# arduino_shield.net
KiCad netlist of a schematic drawn in EAGLE
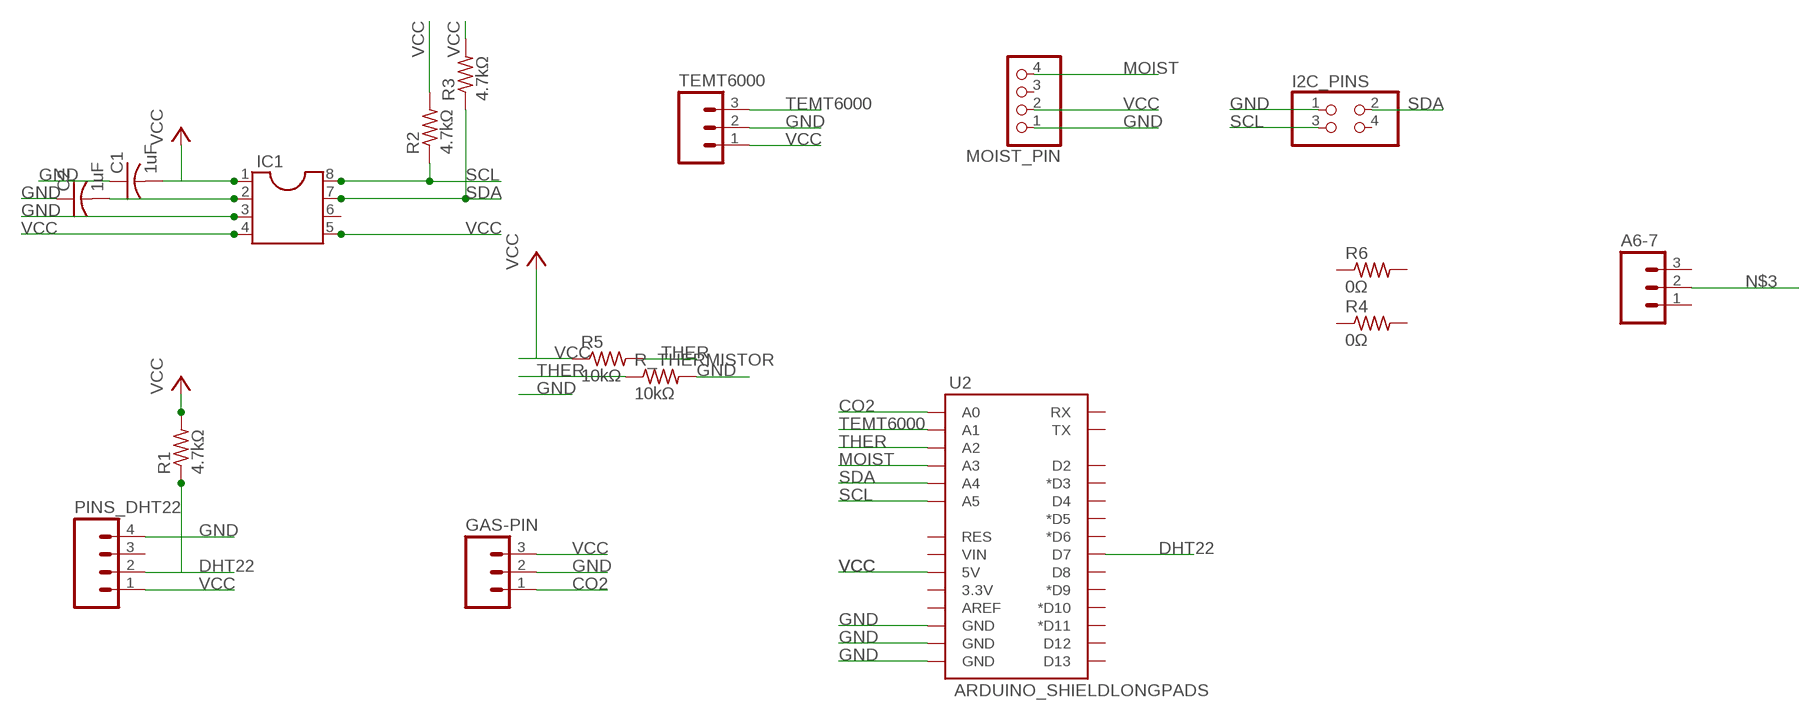
[diagram p0: schematic, sheet 1]

(export (version "E")
  (design (tool "Eeschema 10.0.6"))
  (components
    (comp (ref "A6-7")
      (value "M03LOCK_LONGPADS")
      (footprint "eagle-import:1X03_LOCK_LONGPADS")
      (libsource (lib "eagle-import") (part "M03LOCK_LONGPADS"))
    )
    (comp (ref "C1")
      (value "1uF")
      (footprint "eagle-import:C1206")
      (libsource (lib "eagle-import") (part "C-USC1206"))
    )
    (comp (ref "C2")
      (value "1uF")
      (footprint "eagle-import:C1206")
      (libsource (lib "eagle-import") (part "C-USC1206"))
    )
    (comp (ref "GAS-PIN")
      (value "M03LOCK_LONGPADS")
      (footprint "eagle-import:1X03_LOCK_LONGPADS")
      (libsource (lib "eagle-import") (part "M03LOCK_LONGPADS"))
    )
    (comp (ref "I2C_PINS")
      (value "PINHD-2X2")
      (footprint "eagle-import:2X02")
      (libsource (lib "eagle-import") (part "PINHD-2X2"))
    )
    (comp (ref "IC1")
      (value "DIL8S")
      (footprint "eagle-import:SOCKET-08")
      (libsource (lib "eagle-import") (part "DIL8S"))
    )
    (comp (ref "MOIST_PIN")
      (value "PINHD-1X4M")
      (footprint "eagle-import:1X04M")
      (libsource (lib "eagle-import") (part "PINHD-1X4M"))
    )
    (comp (ref "PINS_DHT22")
      (value "M04LOCK_LONGPADS")
      (footprint "eagle-import:1X04_LOCK_LONGPADS")
      (libsource (lib "eagle-import") (part "M04LOCK_LONGPADS"))
    )
    (comp (ref "R1")
      (value "4.7kΩ")
      (footprint "eagle-import:M1206")
      (libsource (lib "eagle-import") (part "R-US_M1206"))
    )
    (comp (ref "R2")
      (value "4.7kΩ")
      (footprint "eagle-import:M1206")
      (libsource (lib "eagle-import") (part "R-US_M1206"))
    )
    (comp (ref "R3")
      (value "4.7kΩ")
      (footprint "eagle-import:M1206")
      (libsource (lib "eagle-import") (part "R-US_M1206"))
    )
    (comp (ref "R4")
      (value "0Ω")
      (footprint "eagle-import:M1206")
      (libsource (lib "eagle-import") (part "R-US_M1206"))
    )
    (comp (ref "R5")
      (value "10kΩ")
      (footprint "eagle-import:M1206")
      (libsource (lib "eagle-import") (part "R-US_M1206"))
    )
    (comp (ref "R6")
      (value "0Ω")
      (footprint "eagle-import:M1206")
      (libsource (lib "eagle-import") (part "R-US_M1206"))
    )
    (comp (ref "R_THERMISTOR")
      (value "10kΩ")
      (footprint "eagle-import:M1206")
      (libsource (lib "eagle-import") (part "R-US_M1206"))
    )
    (comp (ref "TEMT6000")
      (value "M03LOCK_LONGPADS")
      (footprint "eagle-import:1X03_LOCK_LONGPADS")
      (libsource (lib "eagle-import") (part "M03LOCK_LONGPADS"))
    )
    (comp (ref "U2")
      (value "ARDUINO_SHIELDLONGPADS")
      (footprint "eagle-import:DUEMILANOVE_SHIELD_LONGPADS")
      (libsource (lib "eagle-import") (part "ARDUINO_SHIELDLONGPADS"))
    )
  )
  (nets
    (net (code "1") (name "/CO2") (class "Default")
      (node (ref "GAS-PIN") (pin "1") (pinfunction "1_1") (pintype "passive"))
      (node (ref "U2") (pin "A0") (pinfunction "A0_A0") (pintype "bidirectional"))
    )
    (net (code "2") (name "/DHT22") (class "Default")
      (node (ref "PINS_DHT22") (pin "2") (pinfunction "2_2") (pintype "passive"))
      (node (ref "R1") (pin "1") (pinfunction "1_1") (pintype "passive"))
      (node (ref "U2") (pin "D7") (pinfunction "D7_D7") (pintype "bidirectional"))
    )
    (net (code "3") (name "/GND") (class "Default")
      (node (ref "C1") (pin "1") (pinfunction "1_1") (pintype "passive"))
      (node (ref "C2") (pin "1") (pinfunction "1_1") (pintype "passive"))
      (node (ref "GAS-PIN") (pin "2") (pinfunction "2_2") (pintype "passive"))
      (node (ref "I2C_PINS") (pin "1") (pinfunction "1_1") (pintype "passive"))
      (node (ref "IC1") (pin "3") (pinfunction "3_3") (pintype "passive"))
      (node (ref "MOIST_PIN") (pin "1") (pinfunction "1_1") (pintype "passive"))
      (node (ref "PINS_DHT22") (pin "4") (pinfunction "4_4") (pintype "passive"))
      (node (ref "R_THERMISTOR") (pin "2") (pinfunction "2_2") (pintype "passive"))
      (node (ref "TEMT6000") (pin "2") (pinfunction "2_2") (pintype "passive"))
      (node (ref "U2") (pin "GND@0") (pinfunction "GND_GND@0") (pintype "bidirectional"))
      (node (ref "U2") (pin "GND@1") (pinfunction "GND_GND@1") (pintype "bidirectional"))
      (node (ref "U2") (pin "GND@2") (pinfunction "GND_GND@2") (pintype "bidirectional"))
    )
    (net (code "4") (name "/MOIST") (class "Default")
      (node (ref "MOIST_PIN") (pin "4") (pinfunction "4_4") (pintype "passive"))
      (node (ref "U2") (pin "A3") (pinfunction "A3_A3") (pintype "bidirectional"))
    )
    (net (code "5") (name "/N$3") (class "Default")
      (node (ref "A6-7") (pin "2") (pinfunction "2_2") (pintype "passive"))
    )
    (net (code "6") (name "/SCL") (class "Default")
      (node (ref "I2C_PINS") (pin "3") (pinfunction "3_3") (pintype "passive"))
      (node (ref "IC1") (pin "8") (pinfunction "8_8") (pintype "passive"))
      (node (ref "R2") (pin "1") (pinfunction "1_1") (pintype "passive"))
      (node (ref "U2") (pin "A5") (pinfunction "A5_A5") (pintype "bidirectional"))
    )
    (net (code "7") (name "/SDA") (class "Default")
      (node (ref "I2C_PINS") (pin "2") (pinfunction "2_2") (pintype "passive"))
      (node (ref "IC1") (pin "7") (pinfunction "7_7") (pintype "passive"))
      (node (ref "R3") (pin "1") (pinfunction "1_1") (pintype "passive"))
      (node (ref "U2") (pin "A4") (pinfunction "A4_A4") (pintype "bidirectional"))
    )
    (net (code "8") (name "/TEMT6000") (class "Default")
      (node (ref "TEMT6000") (pin "3") (pinfunction "3_3") (pintype "passive"))
      (node (ref "U2") (pin "A1") (pinfunction "A1_A1") (pintype "bidirectional"))
    )
    (net (code "9") (name "/THER") (class "Default")
      (node (ref "R5") (pin "2") (pinfunction "2_2") (pintype "passive"))
      (node (ref "R_THERMISTOR") (pin "1") (pinfunction "1_1") (pintype "passive"))
      (node (ref "U2") (pin "A2") (pinfunction "A2_A2") (pintype "bidirectional"))
    )
    (net (code "10") (name "Net-(C2-Pad2)") (class "Default")
      (node (ref "C2") (pin "2") (pinfunction "2_2") (pintype "passive"))
      (node (ref "IC1") (pin "2") (pinfunction "2_2") (pintype "passive"))
    )
    (net (code "11") (name "VCC") (class "Default")
      (node (ref "C1") (pin "2") (pinfunction "2_2") (pintype "passive"))
      (node (ref "GAS-PIN") (pin "3") (pinfunction "3_3") (pintype "passive"))
      (node (ref "IC1") (pin "1") (pinfunction "1_1") (pintype "passive"))
      (node (ref "IC1") (pin "4") (pinfunction "4_4") (pintype "passive"))
      (node (ref "IC1") (pin "5") (pinfunction "5_5") (pintype "passive"))
      (node (ref "MOIST_PIN") (pin "2") (pinfunction "2_2") (pintype "passive"))
      (node (ref "PINS_DHT22") (pin "1") (pinfunction "1_1") (pintype "passive"))
      (node (ref "R1") (pin "2") (pinfunction "2_2") (pintype "passive"))
      (node (ref "R2") (pin "2") (pinfunction "2_2") (pintype "passive"))
      (node (ref "R3") (pin "2") (pinfunction "2_2") (pintype "passive"))
      (node (ref "R5") (pin "1") (pinfunction "1_1") (pintype "passive"))
      (node (ref "TEMT6000") (pin "1") (pinfunction "1_1") (pintype "passive"))
      (node (ref "U2") (pin "5V") (pinfunction "5V_5V") (pintype "bidirectional"))
    )
    (net (code "12") (name "unconnected-(A6-7-Pad1)") (class "Default")
      (node (ref "A6-7") (pin "1") (pinfunction "1_1") (pintype "passive"))
    )
    (net (code "13") (name "unconnected-(A6-7-Pad3)") (class "Default")
      (node (ref "A6-7") (pin "3") (pinfunction "3_3") (pintype "passive"))
    )
    (net (code "14") (name "unconnected-(I2C_PINS-Pad4)") (class "Default")
      (node (ref "I2C_PINS") (pin "4") (pinfunction "4_4") (pintype "passive"))
    )
    (net (code "15") (name "unconnected-(IC1-Pad6)") (class "Default")
      (node (ref "IC1") (pin "6") (pinfunction "6_6") (pintype "passive"))
    )
    (net (code "16") (name "unconnected-(MOIST_PIN-Pad3)") (class "Default")
      (node (ref "MOIST_PIN") (pin "3") (pinfunction "3_3") (pintype "passive"))
    )
    (net (code "17") (name "unconnected-(PINS_DHT22-Pad3)") (class "Default")
      (node (ref "PINS_DHT22") (pin "3") (pinfunction "3_3") (pintype "passive"))
    )
    (net (code "18") (name "unconnected-(R4-Pad1)") (class "Default")
      (node (ref "R4") (pin "1") (pinfunction "1_1") (pintype "passive"))
    )
    (net (code "19") (name "unconnected-(R4-Pad2)") (class "Default")
      (node (ref "R4") (pin "2") (pinfunction "2_2") (pintype "passive"))
    )
    (net (code "20") (name "unconnected-(R6-Pad1)") (class "Default")
      (node (ref "R6") (pin "1") (pinfunction "1_1") (pintype "passive"))
    )
    (net (code "21") (name "unconnected-(R6-Pad2)") (class "Default")
      (node (ref "R6") (pin "2") (pinfunction "2_2") (pintype "passive"))
    )
    (net (code "22") (name "unconnected-(U2-*D3-PadD3)") (class "Default")
      (node (ref "U2") (pin "D3") (pinfunction "*D3_D3") (pintype "bidirectional"))
    )
    (net (code "23") (name "unconnected-(U2-*D5-PadD5)") (class "Default")
      (node (ref "U2") (pin "D5") (pinfunction "*D5_D5") (pintype "bidirectional"))
    )
    (net (code "24") (name "unconnected-(U2-*D6-PadD6)") (class "Default")
      (node (ref "U2") (pin "D6") (pinfunction "*D6_D6") (pintype "bidirectional"))
    )
    (net (code "25") (name "unconnected-(U2-*D9-PadD9)") (class "Default")
      (node (ref "U2") (pin "D9") (pinfunction "*D9_D9") (pintype "bidirectional"))
    )
    (net (code "26") (name "unconnected-(U2-*D10-PadD10)") (class "Default")
      (node (ref "U2") (pin "D10") (pinfunction "*D10_D10") (pintype "bidirectional"))
    )
    (net (code "27") (name "unconnected-(U2-*D11-PadD11)") (class "Default")
      (node (ref "U2") (pin "D11") (pinfunction "*D11_D11") (pintype "bidirectional"))
    )
    (net (code "28") (name "unconnected-(U2-Pad3.3V)") (class "Default")
      (node (ref "U2") (pin "3.3V") (pinfunction "3.3V_3.3V") (pintype "bidirectional"))
    )
    (net (code "29") (name "unconnected-(U2-PadAREF)") (class "Default")
      (node (ref "U2") (pin "AREF") (pinfunction "AREF_AREF") (pintype "bidirectional"))
    )
    (net (code "30") (name "unconnected-(U2-PadD2)") (class "Default")
      (node (ref "U2") (pin "D2") (pinfunction "D2_D2") (pintype "bidirectional"))
    )
    (net (code "31") (name "unconnected-(U2-PadD4)") (class "Default")
      (node (ref "U2") (pin "D4") (pinfunction "D4_D4") (pintype "bidirectional"))
    )
    (net (code "32") (name "unconnected-(U2-PadD8)") (class "Default")
      (node (ref "U2") (pin "D8") (pinfunction "D8_D8") (pintype "bidirectional"))
    )
    (net (code "33") (name "unconnected-(U2-PadD12)") (class "Default")
      (node (ref "U2") (pin "D12") (pinfunction "D12_D12") (pintype "bidirectional"))
    )
    (net (code "34") (name "unconnected-(U2-PadD13)") (class "Default")
      (node (ref "U2") (pin "D13") (pinfunction "D13_D13") (pintype "bidirectional"))
    )
    (net (code "35") (name "unconnected-(U2-PadRES)") (class "Default")
      (node (ref "U2") (pin "RES") (pinfunction "RES_RES") (pintype "bidirectional"))
    )
    (net (code "36") (name "unconnected-(U2-PadRX)") (class "Default")
      (node (ref "U2") (pin "RX") (pinfunction "RX_RX") (pintype "bidirectional"))
    )
    (net (code "37") (name "unconnected-(U2-PadTX)") (class "Default")
      (node (ref "U2") (pin "TX") (pinfunction "TX_TX") (pintype "bidirectional"))
    )
    (net (code "38") (name "unconnected-(U2-PadVIN)") (class "Default")
      (node (ref "U2") (pin "VIN") (pinfunction "VIN_VIN") (pintype "bidirectional"))
    )
  )
)
